# STM32F301C8.net
KiCad netlist of a schematic drawn in Altium Designer
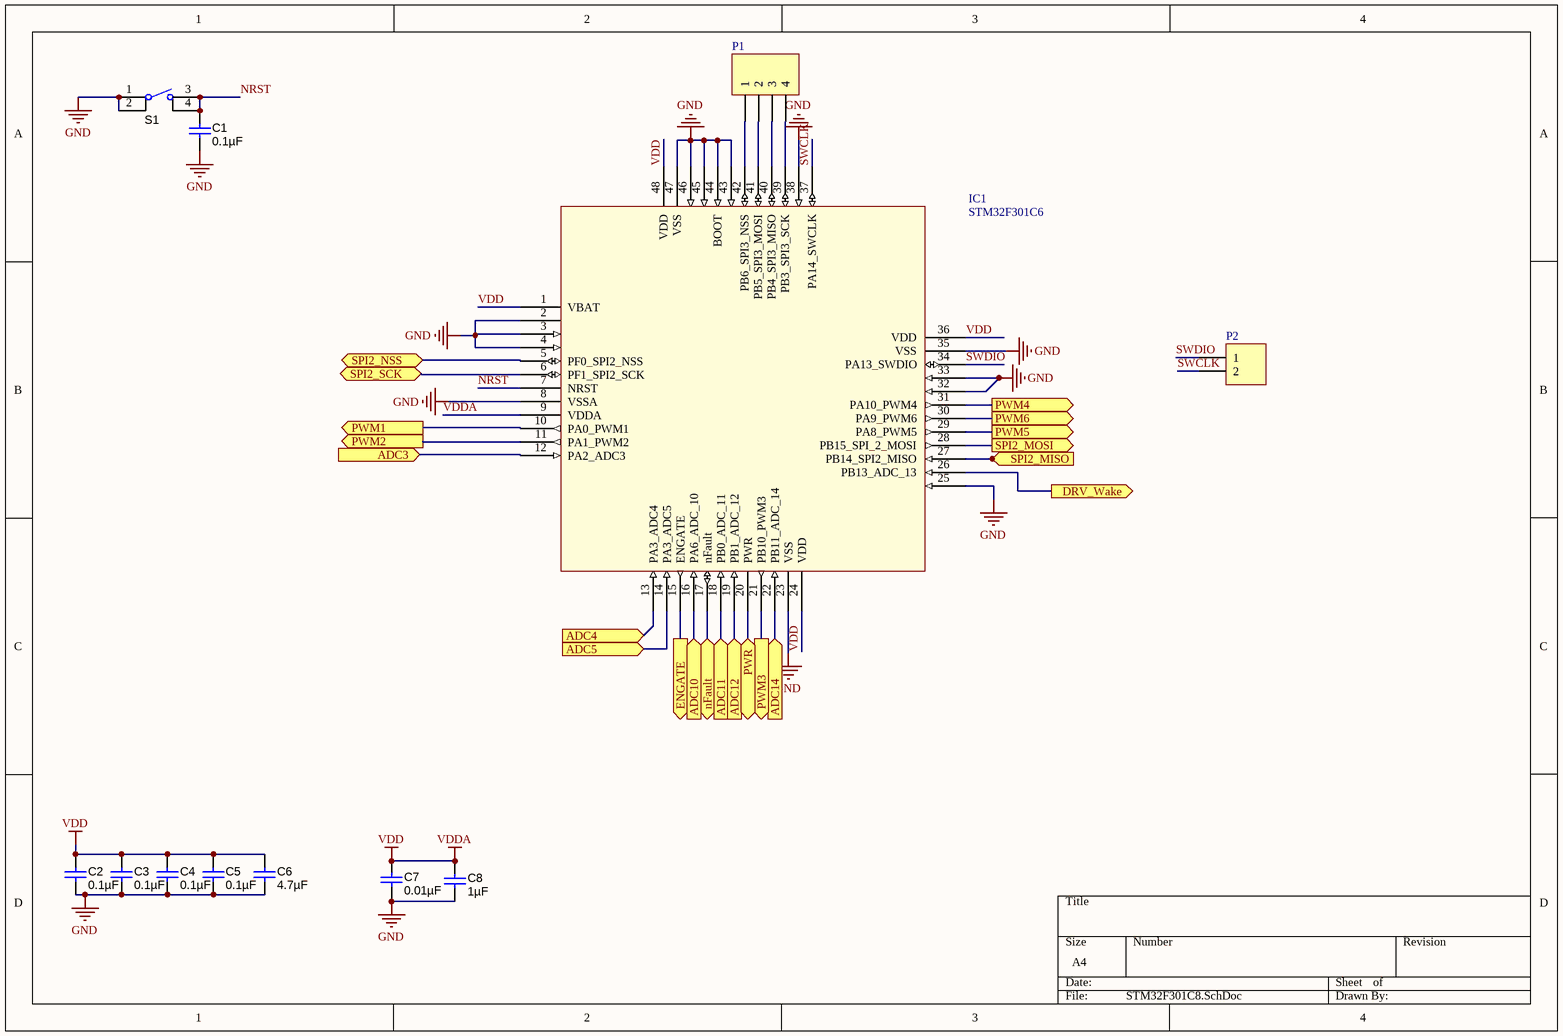
[diagram p0: STM32F301C8.SchDoc]

(export (version "E")
  (design (tool "Eeschema 10.0.6"))
  (components
    (comp (ref "C1")
      (value "C1608X7R1H104K")
      (footprint "0603L")
      (description "CAP, CERM, 0.1 µF, 50 V, +/- 10%, X7R, 0603")
      (fields
        (field (name "VALUEDISPLAYED") "0.1µF")
        (field (name "MANUFACTURER") "TDK")
        (field (name "PUBLISHER") "Texas Instruments")
      )
      (libsource (lib "MDBU014A") (part "C1608X7R1H104K"))
    )
    (comp (ref "C2")
      (value "C1608X7R1H104K")
      (footprint "0603L")
      (description "CAP, CERM, 0.1 µF, 50 V, +/- 10%, X7R, 0603")
      (fields
        (field (name "VALUEDISPLAYED") "0.1µF")
        (field (name "MANUFACTURER") "TDK")
        (field (name "PUBLISHER") "Texas Instruments")
      )
      (libsource (lib "MDBU014A") (part "C1608X7R1H104K"))
    )
    (comp (ref "C3")
      (value "C1608X7R1H104K")
      (footprint "0603L")
      (description "CAP, CERM, 0.1 µF, 50 V, +/- 10%, X7R, 0603")
      (fields
        (field (name "VALUEDISPLAYED") "0.1µF")
        (field (name "MANUFACTURER") "TDK")
        (field (name "PUBLISHER") "Texas Instruments")
      )
      (libsource (lib "MDBU014A") (part "C1608X7R1H104K"))
    )
    (comp (ref "C4")
      (value "C1608X7R1H104K")
      (footprint "0603L")
      (description "CAP, CERM, 0.1 µF, 50 V, +/- 10%, X7R, 0603")
      (fields
        (field (name "VALUEDISPLAYED") "0.1µF")
        (field (name "MANUFACTURER") "TDK")
        (field (name "PUBLISHER") "Texas Instruments")
      )
      (libsource (lib "MDBU014A") (part "C1608X7R1H104K"))
    )
    (comp (ref "C5")
      (value "C1608X7R1H104K")
      (footprint "0603L")
      (description "CAP, CERM, 0.1 µF, 50 V, +/- 10%, X7R, 0603")
      (fields
        (field (name "VALUEDISPLAYED") "0.1µF")
        (field (name "MANUFACTURER") "TDK")
        (field (name "PUBLISHER") "Texas Instruments")
      )
      (libsource (lib "MDBU014A") (part "C1608X7R1H104K"))
    )
    (comp (ref "C6")
      (value "GRM21BR71A475KA73L")
      (footprint "0805L")
      (description "CAP, CERM, 4.7 µF, 10 V, +/- 10%, X7R, 0805")
      (fields
        (field (name "VALUEDISPLAYED") "4.7µF")
        (field (name "MANUFACTURER") "MuRata")
        (field (name "PUBLISHER") "Texas Instruments")
      )
      (libsource (lib "MDBU014A") (part "GRM21BR71A475KA73L"))
    )
    (comp (ref "C7")
      (value "C1608X8R1H103K")
      (footprint "0603L")
      (description "CAP, CERM, 0.01 µF, 50 V, +/- 10%, X8R, 0603")
      (fields
        (field (name "VALUEDISPLAYED") "0.01µF")
        (field (name "MANUFACTURER") "TDK")
        (field (name "PUBLISHER") "Texas Instruments")
      )
      (libsource (lib "MDBU014A") (part "C1608X8R1H103K"))
    )
    (comp (ref "C8")
      (value "C1608X7R1C105K")
      (footprint "0603L")
      (description "CAP, CERM, 1 µF, 16 V, +/- 10%, X7R, 0603")
      (fields
        (field (name "VALUEDISPLAYED") "1µF")
        (field (name "MANUFACTURER") "TDK")
        (field (name "PUBLISHER") "Texas Instruments")
      )
      (libsource (lib "MDBU014A") (part "C1608X7R1C105K"))
    )
    (comp (ref "IC1")
      (value "STM32F301C6")
      (footprint "LQFP48-7x7mm")
      (libsource (lib "AtTiny85") (part "STM32F301C6"))
    )
    (comp (ref "P1")
      (value "~")
      (footprint "HDR1X4")
      (description "Header, 4-Pin")
      (fields (field (name "PUBLISHER") "Altium Limited"))
      (libsource (lib "Miscellaneous Connectors") (part "Header 4"))
    )
    (comp (ref "P2")
      (value "~")
      (footprint "HDR1X2")
      (description "Header, 2-Pin")
      (fields (field (name "PUBLISHER") "Altium Limited"))
      (libsource (lib "Miscellaneous Connectors") (part "Header 2"))
    )
    (comp (ref "S1")
      (value "4-1437565-1")
      (footprint "SW_FSM4JSMA")
      (description "Switch, Tactile, SPST-NO, 0.05A, 12V, SMT")
      (fields
        (field (name "MANUFACTURER") "TE Connectivity")
        (field (name "SYMBOLCREATOR") "a0412235")
        (field (name "PUBLISHER") "Texas Instruments")
      )
      (libsource (lib "MDBU014A") (part "4-1437565-1"))
    )
  )
  (nets
    (net (code "1") (name "/ADC3") (class "Default")
      (node (ref "IC1") (pin "12") (pinfunction "PA2_ADC3_12") (pintype "input"))
    )
    (net (code "2") (name "/ADC4") (class "Default")
      (node (ref "IC1") (pin "13") (pinfunction "PA3_ADC4_13") (pintype "input"))
    )
    (net (code "3") (name "/ADC5") (class "Default")
      (node (ref "IC1") (pin "14") (pinfunction "PA3_ADC5_14") (pintype "input"))
    )
    (net (code "4") (name "/ADC10") (class "Default")
      (node (ref "IC1") (pin "16") (pinfunction "PA6_ADC_10_16") (pintype "input"))
    )
    (net (code "5") (name "/ADC11") (class "Default")
      (node (ref "IC1") (pin "18") (pinfunction "PB0_ADC_11_18") (pintype "input"))
    )
    (net (code "6") (name "/ADC12") (class "Default")
      (node (ref "IC1") (pin "19") (pinfunction "PB1_ADC_12_19") (pintype "input"))
    )
    (net (code "7") (name "/ADC14") (class "Default")
      (node (ref "IC1") (pin "22") (pinfunction "PB11_ADC_14_22") (pintype "input"))
    )
    (net (code "8") (name "/DRV_Wake") (class "Default")
      (node (ref "IC1") (pin "26") (pinfunction "PB13_ADC_13_26") (pintype "input"))
    )
    (net (code "9") (name "/ENGATE") (class "Default")
      (node (ref "IC1") (pin "15") (pinfunction "ENGATE_15") (pintype "output"))
    )
    (net (code "10") (name "/NRST") (class "Default")
      (node (ref "C1") (pin "1") (pinfunction "1_1") (pintype "passive"))
      (node (ref "IC1") (pin "7") (pinfunction "NRST_7") (pintype "power_in"))
      (node (ref "S1") (pin "3") (pinfunction "3_3") (pintype "passive"))
      (node (ref "S1") (pin "4") (pinfunction "4_4") (pintype "passive"))
    )
    (net (code "11") (name "/PWM1") (class "Default")
      (node (ref "IC1") (pin "10") (pinfunction "PA0_PWM1_10") (pintype "output"))
    )
    (net (code "12") (name "/PWM2") (class "Default")
      (node (ref "IC1") (pin "11") (pinfunction "PA1_PWM2_11") (pintype "output"))
    )
    (net (code "13") (name "/PWM3") (class "Default")
      (node (ref "IC1") (pin "21") (pinfunction "PB10_PWM3_21") (pintype "output"))
    )
    (net (code "14") (name "/PWM4") (class "Default")
      (node (ref "IC1") (pin "31") (pinfunction "PA10_PWM4_31") (pintype "output"))
    )
    (net (code "15") (name "/PWM5") (class "Default")
      (node (ref "IC1") (pin "29") (pinfunction "PA8_PWM5_29") (pintype "output"))
    )
    (net (code "16") (name "/PWM6") (class "Default")
      (node (ref "IC1") (pin "30") (pinfunction "PA9_PWM6_30") (pintype "output"))
    )
    (net (code "17") (name "/PWR") (class "Default")
      (node (ref "IC1") (pin "20") (pinfunction "PWR_20") (pintype "passive"))
    )
    (net (code "18") (name "/SPI2_MISO") (class "Default")
      (node (ref "IC1") (pin "27") (pinfunction "PB14_SPI2_MISO_27") (pintype "input"))
    )
    (net (code "19") (name "/SPI2_MOSI") (class "Default")
      (node (ref "IC1") (pin "28") (pinfunction "PB15_SPI_2_MOSI_28") (pintype "output"))
    )
    (net (code "20") (name "/SPI2_NSS") (class "Default")
      (node (ref "IC1") (pin "5") (pinfunction "PF0_SPI2_NSS_5") (pintype "bidirectional"))
    )
    (net (code "21") (name "/SPI2_SCK") (class "Default")
      (node (ref "IC1") (pin "6") (pinfunction "PF1_SPI2_SCK_6") (pintype "bidirectional"))
    )
    (net (code "22") (name "/SWCLK") (class "Default")
      (node (ref "IC1") (pin "37") (pinfunction "PA14_SWCLK_37") (pintype "bidirectional"))
      (node (ref "P2") (pin "2") (pinfunction "2_2") (pintype "passive"))
    )
    (net (code "23") (name "/SWDIO") (class "Default")
      (node (ref "IC1") (pin "34") (pinfunction "PA13_SWDIO_34") (pintype "bidirectional"))
      (node (ref "P2") (pin "1") (pinfunction "1_1") (pintype "passive"))
    )
    (net (code "24") (name "/nFault") (class "Default")
      (node (ref "IC1") (pin "17") (pinfunction "nFault_17") (pintype "bidirectional"))
    )
    (net (code "25") (name "GND") (class "Default")
      (node (ref "C1") (pin "2") (pinfunction "2_2") (pintype "passive"))
      (node (ref "C2") (pin "2") (pinfunction "2_2") (pintype "passive"))
      (node (ref "C3") (pin "2") (pinfunction "2_2") (pintype "passive"))
      (node (ref "C4") (pin "2") (pinfunction "2_2") (pintype "passive"))
      (node (ref "C5") (pin "2") (pinfunction "2_2") (pintype "passive"))
      (node (ref "C6") (pin "2") (pinfunction "2_2") (pintype "passive"))
      (node (ref "C7") (pin "2") (pinfunction "2_2") (pintype "passive"))
      (node (ref "C8") (pin "2") (pinfunction "2_2") (pintype "passive"))
      (node (ref "IC1") (pin "2") (pintype "passive"))
      (node (ref "IC1") (pin "23") (pinfunction "VSS_23") (pintype "power_in"))
      (node (ref "IC1") (pin "25") (pintype "input"))
      (node (ref "IC1") (pin "3") (pintype "input"))
      (node (ref "IC1") (pin "32") (pintype "input"))
      (node (ref "IC1") (pin "33") (pintype "input"))
      (node (ref "IC1") (pin "35") (pinfunction "VSS_35") (pintype "power_in"))
      (node (ref "IC1") (pin "38") (pintype "input"))
      (node (ref "IC1") (pin "4") (pintype "input"))
      (node (ref "IC1") (pin "43") (pintype "input"))
      (node (ref "IC1") (pin "44") (pinfunction "BOOT_44") (pintype "input"))
      (node (ref "IC1") (pin "45") (pintype "input"))
      (node (ref "IC1") (pin "46") (pintype "input"))
      (node (ref "IC1") (pin "47") (pinfunction "VSS_47") (pintype "power_in"))
      (node (ref "IC1") (pin "8") (pinfunction "VSSA_8") (pintype "power_in"))
      (node (ref "S1") (pin "1") (pinfunction "1_1") (pintype "passive"))
      (node (ref "S1") (pin "2") (pinfunction "2_2") (pintype "passive"))
    )
    (net (code "26") (name "Net-(IC1-PB3_SPI3_SCK)") (class "Default")
      (node (ref "IC1") (pin "39") (pinfunction "PB3_SPI3_SCK_39") (pintype "bidirectional"))
      (node (ref "P1") (pin "4") (pinfunction "4_4") (pintype "passive"))
    )
    (net (code "27") (name "Net-(IC1-PB4_SPI3_MISO)") (class "Default")
      (node (ref "IC1") (pin "40") (pinfunction "PB4_SPI3_MISO_40") (pintype "bidirectional"))
      (node (ref "P1") (pin "3") (pinfunction "3_3") (pintype "passive"))
    )
    (net (code "28") (name "Net-(IC1-PB5_SPI3_MOSI)") (class "Default")
      (node (ref "IC1") (pin "41") (pinfunction "PB5_SPI3_MOSI_41") (pintype "bidirectional"))
      (node (ref "P1") (pin "2") (pinfunction "2_2") (pintype "passive"))
    )
    (net (code "29") (name "Net-(IC1-PB6_SPI3_NSS)") (class "Default")
      (node (ref "IC1") (pin "42") (pinfunction "PB6_SPI3_NSS_42") (pintype "bidirectional"))
      (node (ref "P1") (pin "1") (pinfunction "1_1") (pintype "passive"))
    )
    (net (code "30") (name "VDD") (class "Default")
      (node (ref "C2") (pin "1") (pinfunction "1_1") (pintype "passive"))
      (node (ref "C3") (pin "1") (pinfunction "1_1") (pintype "passive"))
      (node (ref "C4") (pin "1") (pinfunction "1_1") (pintype "passive"))
      (node (ref "C5") (pin "1") (pinfunction "1_1") (pintype "passive"))
      (node (ref "C6") (pin "1") (pinfunction "1_1") (pintype "passive"))
      (node (ref "C7") (pin "1") (pinfunction "1_1") (pintype "passive"))
      (node (ref "C8") (pin "1") (pinfunction "1_1") (pintype "passive"))
      (node (ref "IC1") (pin "1") (pinfunction "VBAT_1") (pintype "power_in"))
      (node (ref "IC1") (pin "24") (pinfunction "VDD_24") (pintype "power_in"))
      (node (ref "IC1") (pin "36") (pinfunction "VDD_36") (pintype "power_in"))
      (node (ref "IC1") (pin "48") (pinfunction "VDD_48") (pintype "power_in"))
      (node (ref "IC1") (pin "9") (pinfunction "VDDA_9") (pintype "power_in"))
    )
  )
)
